# design.net
KiCad netlist of a schematic drawn in Altium Designer
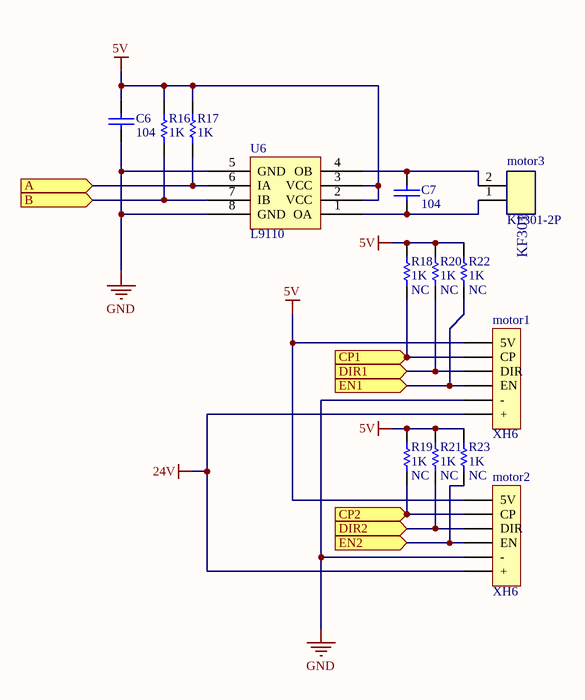
[diagram p0: 驱动模块.SchDoc]

(export (version "E")
  (design (tool "Eeschema 10.0.6"))
  (components
    (comp (ref "C6")
      (value "104")
      (footprint "0603C")
      (description "无极性电容")
      (fields (field (name "Comment") "CAP"))
      (libsource (lib "电容") (part "CAP"))
    )
    (comp (ref "C7")
      (value "104")
      (footprint "0603C")
      (description "无极性电容")
      (fields (field (name "Comment") "CAP"))
      (libsource (lib "电容") (part "CAP"))
    )
    (comp (ref "motor1") (value "XH6") (footprint "XH6/2.54mm/180") (libsource (lib "XH，VH") (part "XH6")))
    (comp (ref "motor2") (value "XH6") (footprint "XH6/2.54mm/180") (libsource (lib "XH，VH") (part "XH6")))
    (comp (ref "motor3")
      (value "KF301-2P")
      (footprint "KF301-5.0-2P")
      (libsource (lib "KF301") (part "KF301-2P"))
    )
    (comp (ref "R16")
      (value "1K")
      (footprint "0603R")
      (fields (field (name "Comment") "RES"))
      (libsource (lib "电阻") (part "RES"))
    )
    (comp (ref "R17")
      (value "1K")
      (footprint "0603R")
      (fields (field (name "Comment") "RES"))
      (libsource (lib "电阻") (part "RES"))
    )
    (comp (ref "R18")
      (value "1K")
      (footprint "0603R")
      (fields (field (name "NOTE") "NC") (field (name "Comment") "RES"))
      (libsource (lib "电阻") (part "RES"))
    )
    (comp (ref "R19")
      (value "1K")
      (footprint "0603R")
      (fields (field (name "NOTE") "NC") (field (name "Comment") "RES"))
      (libsource (lib "电阻") (part "RES"))
    )
    (comp (ref "R20")
      (value "1K")
      (footprint "0603R")
      (fields (field (name "NOTE") "NC") (field (name "Comment") "RES"))
      (libsource (lib "电阻") (part "RES"))
    )
    (comp (ref "R21")
      (value "1K")
      (footprint "0603R")
      (fields (field (name "NOTE") "NC") (field (name "Comment") "RES"))
      (libsource (lib "电阻") (part "RES"))
    )
    (comp (ref "R22")
      (value "1K")
      (footprint "0603R")
      (fields (field (name "NOTE") "NC") (field (name "Comment") "RES"))
      (libsource (lib "电阻") (part "RES"))
    )
    (comp (ref "R23")
      (value "1K")
      (footprint "0603R")
      (fields (field (name "NOTE") "NC") (field (name "Comment") "RES"))
      (libsource (lib "电阻") (part "RES"))
    )
    (comp (ref "U6") (value "L9110") (footprint "SOP8") (libsource (lib "LIB") (part "L9110")))
  )
  (nets
    (net (code "1") (name "/A") (class "Default")
      (node (ref "R17") (pin "2") (pinfunction "2_2") (pintype "passive"))
      (node (ref "U6") (pin "6") (pinfunction "IA_6") (pintype "passive"))
    )
    (net (code "2") (name "/B") (class "Default")
      (node (ref "R16") (pin "2") (pinfunction "2_2") (pintype "passive"))
      (node (ref "U6") (pin "7") (pinfunction "IB_7") (pintype "passive"))
    )
    (net (code "3") (name "/CP1") (class "Default")
      (node (ref "R18") (pin "2") (pinfunction "2_2") (pintype "passive"))
      (node (ref "motor1") (pin "2") (pinfunction "CP_2") (pintype "passive"))
    )
    (net (code "4") (name "/CP2") (class "Default")
      (node (ref "R19") (pin "2") (pinfunction "2_2") (pintype "passive"))
      (node (ref "motor2") (pin "2") (pinfunction "CP_2") (pintype "passive"))
    )
    (net (code "5") (name "/DIR1") (class "Default")
      (node (ref "R20") (pin "1") (pinfunction "1_1") (pintype "passive"))
      (node (ref "motor1") (pin "3") (pinfunction "DIR_3") (pintype "passive"))
    )
    (net (code "6") (name "/DIR2") (class "Default")
      (node (ref "R21") (pin "2") (pinfunction "2_2") (pintype "passive"))
      (node (ref "motor2") (pin "3") (pinfunction "DIR_3") (pintype "passive"))
    )
    (net (code "7") (name "/EN1") (class "Default")
      (node (ref "R22") (pin "2") (pinfunction "2_2") (pintype "passive"))
      (node (ref "motor1") (pin "4") (pinfunction "EN_4") (pintype "passive"))
    )
    (net (code "8") (name "/EN2") (class "Default")
      (node (ref "R23") (pin "2") (pinfunction "2_2") (pintype "passive"))
      (node (ref "motor2") (pin "4") (pinfunction "EN_4") (pintype "passive"))
    )
    (net (code "9") (name "5V") (class "Default")
      (node (ref "C6") (pin "2") (pinfunction "2_2") (pintype "passive"))
      (node (ref "R16") (pin "1") (pinfunction "1_1") (pintype "passive"))
      (node (ref "R17") (pin "1") (pinfunction "1_1") (pintype "passive"))
      (node (ref "R18") (pin "1") (pinfunction "1_1") (pintype "passive"))
      (node (ref "R19") (pin "1") (pinfunction "1_1") (pintype "passive"))
      (node (ref "R20") (pin "2") (pinfunction "2_2") (pintype "passive"))
      (node (ref "R21") (pin "1") (pinfunction "1_1") (pintype "passive"))
      (node (ref "R22") (pin "1") (pinfunction "1_1") (pintype "passive"))
      (node (ref "R23") (pin "1") (pinfunction "1_1") (pintype "passive"))
      (node (ref "U6") (pin "2") (pinfunction "VCC_2") (pintype "passive"))
      (node (ref "U6") (pin "3") (pinfunction "VCC_3") (pintype "passive"))
      (node (ref "motor1") (pin "1") (pinfunction "5V_1") (pintype "passive"))
      (node (ref "motor2") (pin "1") (pinfunction "5V_1") (pintype "passive"))
    )
    (net (code "10") (name "24V") (class "Default")
      (node (ref "motor1") (pin "6") (pinfunction "+_6") (pintype "passive"))
      (node (ref "motor2") (pin "6") (pinfunction "+_6") (pintype "passive"))
    )
    (net (code "11") (name "GND") (class "Default")
      (node (ref "C6") (pin "1") (pinfunction "1_1") (pintype "passive"))
      (node (ref "U6") (pin "5") (pinfunction "GND_5") (pintype "passive"))
      (node (ref "U6") (pin "8") (pinfunction "GND_8") (pintype "passive"))
      (node (ref "motor1") (pin "5") (pinfunction "-_5") (pintype "passive"))
      (node (ref "motor2") (pin "5") (pinfunction "-_5") (pintype "passive"))
    )
    (net (code "12") (name "Net-(U6-OA)") (class "Default")
      (node (ref "C7") (pin "1") (pinfunction "1_1") (pintype "passive"))
      (node (ref "U6") (pin "1") (pinfunction "OA_1") (pintype "passive"))
      (node (ref "motor3") (pin "1") (pinfunction "1_1") (pintype "passive"))
    )
    (net (code "13") (name "Net-(U6-OB)") (class "Default")
      (node (ref "C7") (pin "2") (pinfunction "2_2") (pintype "passive"))
      (node (ref "U6") (pin "4") (pinfunction "OB_4") (pintype "passive"))
      (node (ref "motor3") (pin "2") (pinfunction "2_2") (pintype "passive"))
    )
  )
)
